# 3__Output_Feedback.net
KiCad netlist of a schematic drawn in Altium Designer
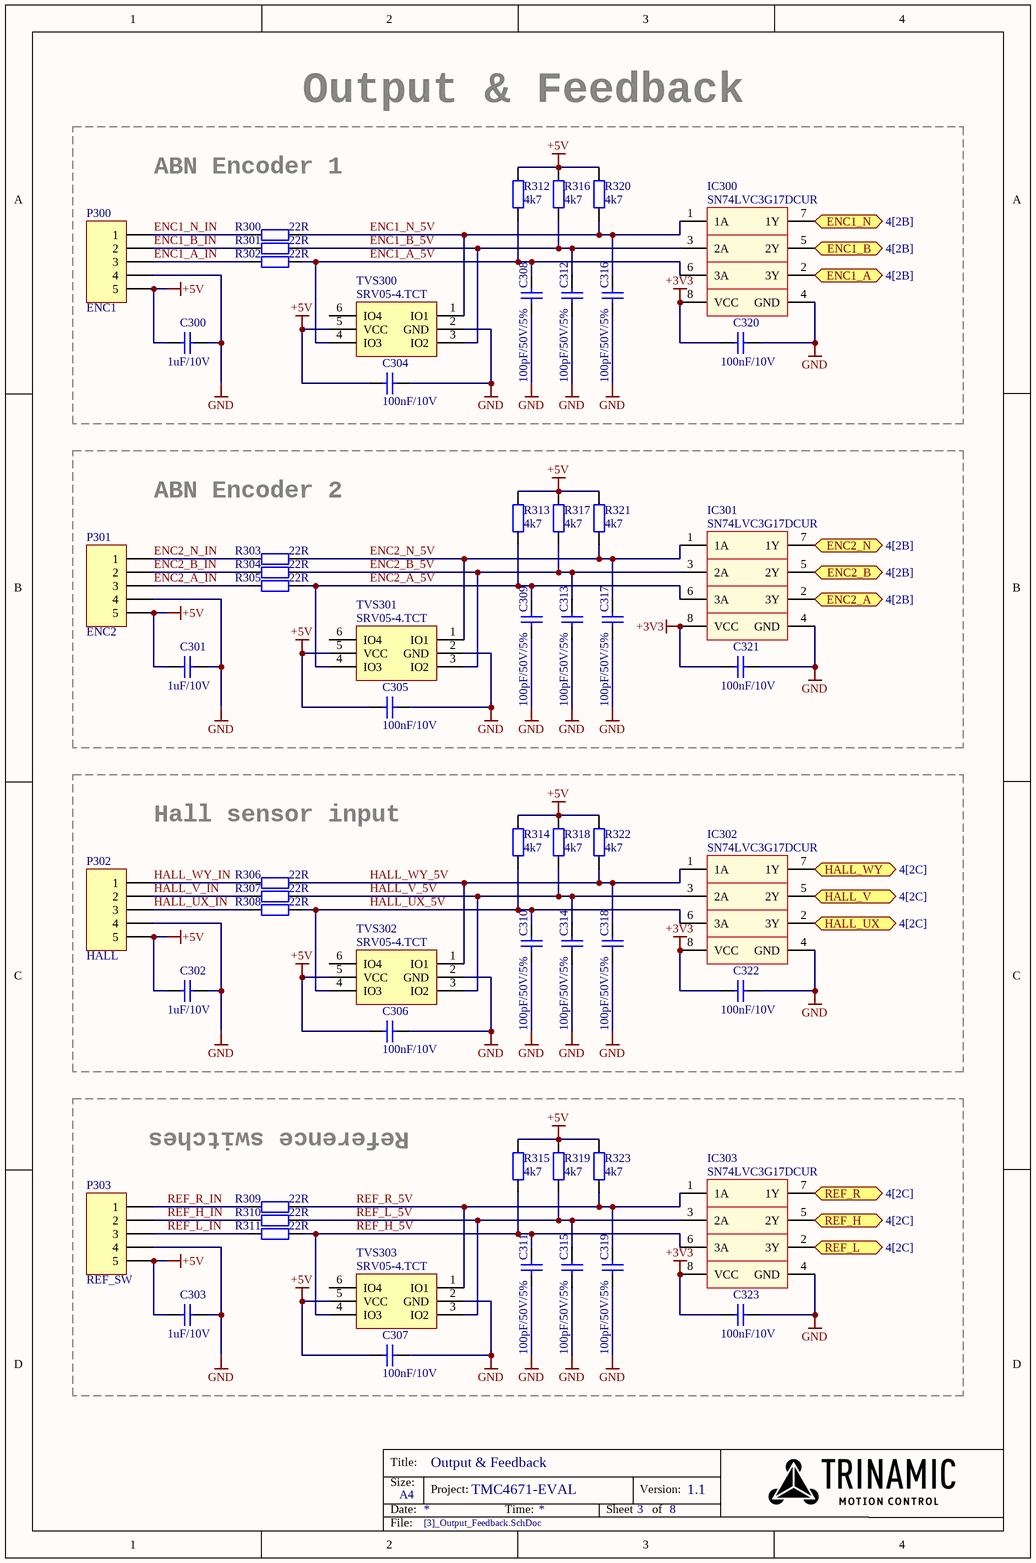
[diagram p0: [3]_Output_Feedback.SchDoc]

(export (version "E")
  (design (tool "Eeschema 10.0.6"))
  (components
    (comp (ref "C300")
      (value "1uF/10V")
      (footprint "C0603")
      (description "SMD Multilayer Ceramic Capacitor, 0603 [1608 Metric], 1 µF, 10 V, ± 10%, X5R, MC Series")
      (fields (field (name "MF") "MULTICOMP") (field (name "MPN") "MC0603X105K100CT"))
      (libsource (lib "SMD_Passives") (part "C, 1 µF, 10 V, ± 10%, X5R, MC Series, 0603 [1608 Metric]"))
    )
    (comp (ref "C301")
      (value "1uF/10V")
      (footprint "C0603")
      (description "SMD Multilayer Ceramic Capacitor, 0603 [1608 Metric], 1 µF, 10 V, ± 10%, X5R, MC Series")
      (fields (field (name "MF") "MULTICOMP") (field (name "MPN") "MC0603X105K100CT"))
      (libsource (lib "SMD_Passives") (part "C, 1 µF, 10 V, ± 10%, X5R, MC Series, 0603 [1608 Metric]"))
    )
    (comp (ref "C302")
      (value "1uF/10V")
      (footprint "C0603")
      (description "SMD Multilayer Ceramic Capacitor, 0603 [1608 Metric], 1 µF, 10 V, ± 10%, X5R, MC Series")
      (fields (field (name "MF") "MULTICOMP") (field (name "MPN") "MC0603X105K100CT"))
      (libsource (lib "SMD_Passives") (part "C, 1 µF, 10 V, ± 10%, X5R, MC Series, 0603 [1608 Metric]"))
    )
    (comp (ref "C303")
      (value "1uF/10V")
      (footprint "C0603")
      (description "SMD Multilayer Ceramic Capacitor, 0603 [1608 Metric], 1 µF, 10 V, ± 10%, X5R, MC Series")
      (fields (field (name "MF") "MULTICOMP") (field (name "MPN") "MC0603X105K100CT"))
      (libsource (lib "SMD_Passives") (part "C, 1 µF, 10 V, ± 10%, X5R, MC Series, 0603 [1608 Metric]"))
    )
    (comp (ref "C304")
      (value "100nF/10V")
      (footprint "C0603")
      (description "SMD Multilayer Ceramic Capacitor, 0603 [1608 Metric], 0.1 µF, 10 V, ± 10%, X7R, MC Series")
      (fields (field (name "MF") "Multicomp") (field (name "MPN") "MC0603B104K100CT"))
      (libsource (lib "SMD_Passives") (part "C, 0.1 µF, 10 V, ± 10%, X7R, 0603"))
    )
    (comp (ref "C305")
      (value "100nF/10V")
      (footprint "C0603")
      (description "SMD Multilayer Ceramic Capacitor, 0603 [1608 Metric], 0.1 µF, 10 V, ± 10%, X7R, MC Series")
      (fields (field (name "MF") "Multicomp") (field (name "MPN") "MC0603B104K100CT"))
      (libsource (lib "SMD_Passives") (part "C, 0.1 µF, 10 V, ± 10%, X7R, 0603"))
    )
    (comp (ref "C306")
      (value "100nF/10V")
      (footprint "C0603")
      (description "SMD Multilayer Ceramic Capacitor, 0603 [1608 Metric], 0.1 µF, 10 V, ± 10%, X7R, MC Series")
      (fields (field (name "MF") "Multicomp") (field (name "MPN") "MC0603B104K100CT"))
      (libsource (lib "SMD_Passives") (part "C, 0.1 µF, 10 V, ± 10%, X7R, 0603"))
    )
    (comp (ref "C307")
      (value "100nF/10V")
      (footprint "C0603")
      (description "SMD Multilayer Ceramic Capacitor, 0603 [1608 Metric], 0.1 µF, 10 V, ± 10%, X7R, MC Series")
      (fields (field (name "MF") "Multicomp") (field (name "MPN") "MC0603B104K100CT"))
      (libsource (lib "SMD_Passives") (part "C, 0.1 µF, 10 V, ± 10%, X7R, 0603"))
    )
    (comp (ref "C308")
      (value "100pF/50V/5%")
      (footprint "C0603")
      (description "SMD Multilayer Ceramic Capacitor, 0603 [1608 Metric], 100 pF, 50 V, ± 5%, C0G / NP0, MC Series")
      (fields (field (name "MF") "MULTICOMP") (field (name "MPN") "MC0603N101J500CT"))
      (libsource (lib "SMD_Passives") (part "C, 100 pF, 50 V, ± 5%, C0G / NP0, MC Series, 0603 [1608 Metric]"))
    )
    (comp (ref "C309")
      (value "100pF/50V/5%")
      (footprint "C0603")
      (description "SMD Multilayer Ceramic Capacitor, 0603 [1608 Metric], 100 pF, 50 V, ± 5%, C0G / NP0, MC Series")
      (fields (field (name "MF") "MULTICOMP") (field (name "MPN") "MC0603N101J500CT"))
      (libsource (lib "SMD_Passives") (part "C, 100 pF, 50 V, ± 5%, C0G / NP0, MC Series, 0603 [1608 Metric]"))
    )
    (comp (ref "C310")
      (value "100pF/50V/5%")
      (footprint "C0603")
      (description "SMD Multilayer Ceramic Capacitor, 0603 [1608 Metric], 100 pF, 50 V, ± 5%, C0G / NP0, MC Series")
      (fields (field (name "MF") "MULTICOMP") (field (name "MPN") "MC0603N101J500CT"))
      (libsource (lib "SMD_Passives") (part "C, 100 pF, 50 V, ± 5%, C0G / NP0, MC Series, 0603 [1608 Metric]"))
    )
    (comp (ref "C311")
      (value "100pF/50V/5%")
      (footprint "C0603")
      (description "SMD Multilayer Ceramic Capacitor, 0603 [1608 Metric], 100 pF, 50 V, ± 5%, C0G / NP0, MC Series")
      (fields (field (name "MF") "MULTICOMP") (field (name "MPN") "MC0603N101J500CT"))
      (libsource (lib "SMD_Passives") (part "C, 100 pF, 50 V, ± 5%, C0G / NP0, MC Series, 0603 [1608 Metric]"))
    )
    (comp (ref "C312")
      (value "100pF/50V/5%")
      (footprint "C0603")
      (description "SMD Multilayer Ceramic Capacitor, 0603 [1608 Metric], 100 pF, 50 V, ± 5%, C0G / NP0, MC Series")
      (fields (field (name "MF") "MULTICOMP") (field (name "MPN") "MC0603N101J500CT"))
      (libsource (lib "SMD_Passives") (part "C, 100 pF, 50 V, ± 5%, C0G / NP0, MC Series, 0603 [1608 Metric]"))
    )
    (comp (ref "C313")
      (value "100pF/50V/5%")
      (footprint "C0603")
      (description "SMD Multilayer Ceramic Capacitor, 0603 [1608 Metric], 100 pF, 50 V, ± 5%, C0G / NP0, MC Series")
      (fields (field (name "MF") "MULTICOMP") (field (name "MPN") "MC0603N101J500CT"))
      (libsource (lib "SMD_Passives") (part "C, 100 pF, 50 V, ± 5%, C0G / NP0, MC Series, 0603 [1608 Metric]"))
    )
    (comp (ref "C314")
      (value "100pF/50V/5%")
      (footprint "C0603")
      (description "SMD Multilayer Ceramic Capacitor, 0603 [1608 Metric], 100 pF, 50 V, ± 5%, C0G / NP0, MC Series")
      (fields (field (name "MF") "MULTICOMP") (field (name "MPN") "MC0603N101J500CT"))
      (libsource (lib "SMD_Passives") (part "C, 100 pF, 50 V, ± 5%, C0G / NP0, MC Series, 0603 [1608 Metric]"))
    )
    (comp (ref "C315")
      (value "100pF/50V/5%")
      (footprint "C0603")
      (description "SMD Multilayer Ceramic Capacitor, 0603 [1608 Metric], 100 pF, 50 V, ± 5%, C0G / NP0, MC Series")
      (fields (field (name "MF") "MULTICOMP") (field (name "MPN") "MC0603N101J500CT"))
      (libsource (lib "SMD_Passives") (part "C, 100 pF, 50 V, ± 5%, C0G / NP0, MC Series, 0603 [1608 Metric]"))
    )
    (comp (ref "C316")
      (value "100pF/50V/5%")
      (footprint "C0603")
      (description "SMD Multilayer Ceramic Capacitor, 0603 [1608 Metric], 100 pF, 50 V, ± 5%, C0G / NP0, MC Series")
      (fields (field (name "MF") "MULTICOMP") (field (name "MPN") "MC0603N101J500CT"))
      (libsource (lib "SMD_Passives") (part "C, 100 pF, 50 V, ± 5%, C0G / NP0, MC Series, 0603 [1608 Metric]"))
    )
    (comp (ref "C317")
      (value "100pF/50V/5%")
      (footprint "C0603")
      (description "SMD Multilayer Ceramic Capacitor, 0603 [1608 Metric], 100 pF, 50 V, ± 5%, C0G / NP0, MC Series")
      (fields (field (name "MF") "MULTICOMP") (field (name "MPN") "MC0603N101J500CT"))
      (libsource (lib "SMD_Passives") (part "C, 100 pF, 50 V, ± 5%, C0G / NP0, MC Series, 0603 [1608 Metric]"))
    )
    (comp (ref "C318")
      (value "100pF/50V/5%")
      (footprint "C0603")
      (description "SMD Multilayer Ceramic Capacitor, 0603 [1608 Metric], 100 pF, 50 V, ± 5%, C0G / NP0, MC Series")
      (fields (field (name "MF") "MULTICOMP") (field (name "MPN") "MC0603N101J500CT"))
      (libsource (lib "SMD_Passives") (part "C, 100 pF, 50 V, ± 5%, C0G / NP0, MC Series, 0603 [1608 Metric]"))
    )
    (comp (ref "C319")
      (value "100pF/50V/5%")
      (footprint "C0603")
      (description "SMD Multilayer Ceramic Capacitor, 0603 [1608 Metric], 100 pF, 50 V, ± 5%, C0G / NP0, MC Series")
      (fields (field (name "MF") "MULTICOMP") (field (name "MPN") "MC0603N101J500CT"))
      (libsource (lib "SMD_Passives") (part "C, 100 pF, 50 V, ± 5%, C0G / NP0, MC Series, 0603 [1608 Metric]"))
    )
    (comp (ref "C320")
      (value "100nF/10V")
      (footprint "C0603")
      (description "SMD Multilayer Ceramic Capacitor, 0603 [1608 Metric], 0.1 µF, 10 V, ± 10%, X7R, MC Series")
      (fields (field (name "MF") "Multicomp") (field (name "MPN") "MC0603B104K100CT"))
      (libsource (lib "SMD_Passives") (part "C, 0.1 µF, 10 V, ± 10%, X7R, 0603"))
    )
    (comp (ref "C321")
      (value "100nF/10V")
      (footprint "C0603")
      (description "SMD Multilayer Ceramic Capacitor, 0603 [1608 Metric], 0.1 µF, 10 V, ± 10%, X7R, MC Series")
      (fields (field (name "MF") "Multicomp") (field (name "MPN") "MC0603B104K100CT"))
      (libsource (lib "SMD_Passives") (part "C, 0.1 µF, 10 V, ± 10%, X7R, 0603"))
    )
    (comp (ref "C322")
      (value "100nF/10V")
      (footprint "C0603")
      (description "SMD Multilayer Ceramic Capacitor, 0603 [1608 Metric], 0.1 µF, 10 V, ± 10%, X7R, MC Series")
      (fields (field (name "MF") "Multicomp") (field (name "MPN") "MC0603B104K100CT"))
      (libsource (lib "SMD_Passives") (part "C, 0.1 µF, 10 V, ± 10%, X7R, 0603"))
    )
    (comp (ref "C323")
      (value "100nF/10V")
      (footprint "C0603")
      (description "SMD Multilayer Ceramic Capacitor, 0603 [1608 Metric], 0.1 µF, 10 V, ± 10%, X7R, MC Series")
      (fields (field (name "MF") "Multicomp") (field (name "MPN") "MC0603B104K100CT"))
      (libsource (lib "SMD_Passives") (part "C, 0.1 µF, 10 V, ± 10%, X7R, 0603"))
    )
    (comp (ref "IC300")
      (value "SN74LVC3G17DCUR")
      (footprint "TSSOP50P310X90-8L")
      (description "Triple Schmitt-Trigger Buffer, 74LVC3G17, 1.65 V to 5.5 V, VSSOP-8")
      (fields (field (name "MF") "TEXAS INSTRUMENTS"))
      (libsource (lib "TMC4671-EVAL_V1_0") (part "SN74LVC3G17DCUR"))
    )
    (comp (ref "IC301")
      (value "SN74LVC3G17DCUR")
      (footprint "TSSOP50P310X90-8L")
      (description "Triple Schmitt-Trigger Buffer, 74LVC3G17, 1.65 V to 5.5 V, VSSOP-8")
      (fields (field (name "MF") "TEXAS INSTRUMENTS"))
      (libsource (lib "TMC4671-EVAL_V1_0") (part "SN74LVC3G17DCUR"))
    )
    (comp (ref "IC302")
      (value "SN74LVC3G17DCUR")
      (footprint "TSSOP50P310X90-8L")
      (description "Triple Schmitt-Trigger Buffer, 74LVC3G17, 1.65 V to 5.5 V, VSSOP-8")
      (fields (field (name "MF") "TEXAS INSTRUMENTS"))
      (libsource (lib "TMC4671-EVAL_V1_0") (part "SN74LVC3G17DCUR"))
    )
    (comp (ref "IC303")
      (value "SN74LVC3G17DCUR")
      (footprint "TSSOP50P310X90-8L")
      (description "Triple Schmitt-Trigger Buffer, 74LVC3G17, 1.65 V to 5.5 V, VSSOP-8")
      (fields (field (name "MF") "TEXAS INSTRUMENTS"))
      (libsource (lib "TMC4671-EVAL_V1_0") (part "SN74LVC3G17DCUR"))
    )
    (comp (ref "P300")
      (value "ENC1")
      (footprint "TH_HDR_1X5")
      (description "Header, 5-Pin")
      (libsource (lib "Miscellaneous Connectors") (part "Header 5"))
    )
    (comp (ref "P301")
      (value "ENC2")
      (footprint "TH_HDR_1X5")
      (description "Header, 5-Pin")
      (libsource (lib "Miscellaneous Connectors") (part "Header 5"))
    )
    (comp (ref "P302")
      (value "HALL")
      (footprint "TH_HDR_1X5")
      (description "Header, 5-Pin")
      (libsource (lib "Miscellaneous Connectors") (part "Header 5"))
    )
    (comp (ref "P303")
      (value "REF_SW")
      (footprint "TH_HDR_1X5")
      (description "Header, 5-Pin")
      (libsource (lib "Miscellaneous Connectors") (part "Header 5"))
    )
    (comp (ref "R300")
      (value "22R")
      (footprint "R0603")
      (description "SMD Chip Resistor, Thick Film, 22 ohm, 50 V, 0603 [1608 Metric], 100 mW, ± 1%, MCWR Series")
      (fields
        (field (name "MPN") "MCWR06X22R0FTL")
        (field (name "MF") "MULTICOMP")
        (field (name "RESISTANCE") "22R")
      )
      (libsource (lib "SMD_Passives") (part "R, 22 ohm, 50 V, 0603 [1608 Metric], 100 mW, ± 1%, MCWR Series"))
    )
    (comp (ref "R301")
      (value "22R")
      (footprint "R0603")
      (description "SMD Chip Resistor, Thick Film, 22 ohm, 50 V, 0603 [1608 Metric], 100 mW, ± 1%, MCWR Series")
      (fields
        (field (name "MPN") "MCWR06X22R0FTL")
        (field (name "MF") "MULTICOMP")
        (field (name "RESISTANCE") "22R")
      )
      (libsource (lib "SMD_Passives") (part "R, 22 ohm, 50 V, 0603 [1608 Metric], 100 mW, ± 1%, MCWR Series"))
    )
    (comp (ref "R302")
      (value "22R")
      (footprint "R0603")
      (description "SMD Chip Resistor, Thick Film, 22 ohm, 50 V, 0603 [1608 Metric], 100 mW, ± 1%, MCWR Series")
      (fields
        (field (name "MPN") "MCWR06X22R0FTL")
        (field (name "MF") "MULTICOMP")
        (field (name "RESISTANCE") "22R")
      )
      (libsource (lib "SMD_Passives") (part "R, 22 ohm, 50 V, 0603 [1608 Metric], 100 mW, ± 1%, MCWR Series"))
    )
    (comp (ref "R303")
      (value "22R")
      (footprint "R0603")
      (description "SMD Chip Resistor, Thick Film, 22 ohm, 50 V, 0603 [1608 Metric], 100 mW, ± 1%, MCWR Series")
      (fields
        (field (name "MPN") "MCWR06X22R0FTL")
        (field (name "MF") "MULTICOMP")
        (field (name "RESISTANCE") "22R")
      )
      (libsource (lib "SMD_Passives") (part "R, 22 ohm, 50 V, 0603 [1608 Metric], 100 mW, ± 1%, MCWR Series"))
    )
    (comp (ref "R304")
      (value "22R")
      (footprint "R0603")
      (description "SMD Chip Resistor, Thick Film, 22 ohm, 50 V, 0603 [1608 Metric], 100 mW, ± 1%, MCWR Series")
      (fields
        (field (name "MPN") "MCWR06X22R0FTL")
        (field (name "MF") "MULTICOMP")
        (field (name "RESISTANCE") "22R")
      )
      (libsource (lib "SMD_Passives") (part "R, 22 ohm, 50 V, 0603 [1608 Metric], 100 mW, ± 1%, MCWR Series"))
    )
    (comp (ref "R305")
      (value "22R")
      (footprint "R0603")
      (description "SMD Chip Resistor, Thick Film, 22 ohm, 50 V, 0603 [1608 Metric], 100 mW, ± 1%, MCWR Series")
      (fields
        (field (name "MPN") "MCWR06X22R0FTL")
        (field (name "MF") "MULTICOMP")
        (field (name "RESISTANCE") "22R")
      )
      (libsource (lib "SMD_Passives") (part "R, 22 ohm, 50 V, 0603 [1608 Metric], 100 mW, ± 1%, MCWR Series"))
    )
    (comp (ref "R306")
      (value "22R")
      (footprint "R0603")
      (description "SMD Chip Resistor, Thick Film, 22 ohm, 50 V, 0603 [1608 Metric], 100 mW, ± 1%, MCWR Series")
      (fields
        (field (name "MPN") "MCWR06X22R0FTL")
        (field (name "MF") "MULTICOMP")
        (field (name "RESISTANCE") "22R")
      )
      (libsource (lib "SMD_Passives") (part "R, 22 ohm, 50 V, 0603 [1608 Metric], 100 mW, ± 1%, MCWR Series"))
    )
    (comp (ref "R307")
      (value "22R")
      (footprint "R0603")
      (description "SMD Chip Resistor, Thick Film, 22 ohm, 50 V, 0603 [1608 Metric], 100 mW, ± 1%, MCWR Series")
      (fields
        (field (name "MPN") "MCWR06X22R0FTL")
        (field (name "MF") "MULTICOMP")
        (field (name "RESISTANCE") "22R")
      )
      (libsource (lib "SMD_Passives") (part "R, 22 ohm, 50 V, 0603 [1608 Metric], 100 mW, ± 1%, MCWR Series"))
    )
    (comp (ref "R308")
      (value "22R")
      (footprint "R0603")
      (description "SMD Chip Resistor, Thick Film, 22 ohm, 50 V, 0603 [1608 Metric], 100 mW, ± 1%, MCWR Series")
      (fields
        (field (name "MPN") "MCWR06X22R0FTL")
        (field (name "MF") "MULTICOMP")
        (field (name "RESISTANCE") "22R")
      )
      (libsource (lib "SMD_Passives") (part "R, 22 ohm, 50 V, 0603 [1608 Metric], 100 mW, ± 1%, MCWR Series"))
    )
    (comp (ref "R309")
      (value "22R")
      (footprint "R0603")
      (description "SMD Chip Resistor, Thick Film, 22 ohm, 50 V, 0603 [1608 Metric], 100 mW, ± 1%, MCWR Series")
      (fields
        (field (name "MPN") "MCWR06X22R0FTL")
        (field (name "MF") "MULTICOMP")
        (field (name "RESISTANCE") "22R")
      )
      (libsource (lib "SMD_Passives") (part "R, 22 ohm, 50 V, 0603 [1608 Metric], 100 mW, ± 1%, MCWR Series"))
    )
    (comp (ref "R310")
      (value "22R")
      (footprint "R0603")
      (description "SMD Chip Resistor, Thick Film, 22 ohm, 50 V, 0603 [1608 Metric], 100 mW, ± 1%, MCWR Series")
      (fields
        (field (name "MPN") "MCWR06X22R0FTL")
        (field (name "MF") "MULTICOMP")
        (field (name "RESISTANCE") "22R")
      )
      (libsource (lib "SMD_Passives") (part "R, 22 ohm, 50 V, 0603 [1608 Metric], 100 mW, ± 1%, MCWR Series"))
    )
    (comp (ref "R311")
      (value "22R")
      (footprint "R0603")
      (description "SMD Chip Resistor, Thick Film, 22 ohm, 50 V, 0603 [1608 Metric], 100 mW, ± 1%, MCWR Series")
      (fields
        (field (name "MPN") "MCWR06X22R0FTL")
        (field (name "MF") "MULTICOMP")
        (field (name "RESISTANCE") "22R")
      )
      (libsource (lib "SMD_Passives") (part "R, 22 ohm, 50 V, 0603 [1608 Metric], 100 mW, ± 1%, MCWR Series"))
    )
    (comp (ref "R312")
      (value "4k7")
      (footprint "R0603")
      (description "SMD Chip Resistor, 4.7 kohm, 75 V, 0603 [1608 Metric], 100 mW, ± 1%, WR06 Series")
      (fields
        (field (name "MPN") "WR06X4701FTL")
        (field (name "MF") "WALSIN")
        (field (name "RESISTANCE") "4k7")
      )
      (libsource (lib "SMD_Passives") (part "R, 4.7 kohm, 75 V, 0603 [1608 Metric], 100 mW, ± 1%, WR06 Series"))
    )
    (comp (ref "R313")
      (value "4k7")
      (footprint "R0603")
      (description "SMD Chip Resistor, 4.7 kohm, 75 V, 0603 [1608 Metric], 100 mW, ± 1%, WR06 Series")
      (fields
        (field (name "MPN") "WR06X4701FTL")
        (field (name "MF") "WALSIN")
        (field (name "RESISTANCE") "4k7")
      )
      (libsource (lib "SMD_Passives") (part "R, 4.7 kohm, 75 V, 0603 [1608 Metric], 100 mW, ± 1%, WR06 Series"))
    )
    (comp (ref "R314")
      (value "4k7")
      (footprint "R0603")
      (description "SMD Chip Resistor, 4.7 kohm, 75 V, 0603 [1608 Metric], 100 mW, ± 1%, WR06 Series")
      (fields
        (field (name "MPN") "WR06X4701FTL")
        (field (name "MF") "WALSIN")
        (field (name "RESISTANCE") "4k7")
      )
      (libsource (lib "SMD_Passives") (part "R, 4.7 kohm, 75 V, 0603 [1608 Metric], 100 mW, ± 1%, WR06 Series"))
    )
    (comp (ref "R315")
      (value "4k7")
      (footprint "R0603")
      (description "SMD Chip Resistor, 4.7 kohm, 75 V, 0603 [1608 Metric], 100 mW, ± 1%, WR06 Series")
      (fields
        (field (name "MPN") "WR06X4701FTL")
        (field (name "MF") "WALSIN")
        (field (name "RESISTANCE") "4k7")
      )
      (libsource (lib "SMD_Passives") (part "R, 4.7 kohm, 75 V, 0603 [1608 Metric], 100 mW, ± 1%, WR06 Series"))
    )
    (comp (ref "R316")
      (value "4k7")
      (footprint "R0603")
      (description "SMD Chip Resistor, 4.7 kohm, 75 V, 0603 [1608 Metric], 100 mW, ± 1%, WR06 Series")
      (fields
        (field (name "MPN") "WR06X4701FTL")
        (field (name "MF") "WALSIN")
        (field (name "RESISTANCE") "4k7")
      )
      (libsource (lib "SMD_Passives") (part "R, 4.7 kohm, 75 V, 0603 [1608 Metric], 100 mW, ± 1%, WR06 Series"))
    )
    (comp (ref "R317")
      (value "4k7")
      (footprint "R0603")
      (description "SMD Chip Resistor, 4.7 kohm, 75 V, 0603 [1608 Metric], 100 mW, ± 1%, WR06 Series")
      (fields
        (field (name "MPN") "WR06X4701FTL")
        (field (name "MF") "WALSIN")
        (field (name "RESISTANCE") "4k7")
      )
      (libsource (lib "SMD_Passives") (part "R, 4.7 kohm, 75 V, 0603 [1608 Metric], 100 mW, ± 1%, WR06 Series"))
    )
    (comp (ref "R318")
      (value "4k7")
      (footprint "R0603")
      (description "SMD Chip Resistor, 4.7 kohm, 75 V, 0603 [1608 Metric], 100 mW, ± 1%, WR06 Series")
      (fields
        (field (name "MPN") "WR06X4701FTL")
        (field (name "MF") "WALSIN")
        (field (name "RESISTANCE") "4k7")
      )
      (libsource (lib "SMD_Passives") (part "R, 4.7 kohm, 75 V, 0603 [1608 Metric], 100 mW, ± 1%, WR06 Series"))
    )
    (comp (ref "R319")
      (value "4k7")
      (footprint "R0603")
      (description "SMD Chip Resistor, 4.7 kohm, 75 V, 0603 [1608 Metric], 100 mW, ± 1%, WR06 Series")
      (fields
        (field (name "MPN") "WR06X4701FTL")
        (field (name "MF") "WALSIN")
        (field (name "RESISTANCE") "4k7")
      )
      (libsource (lib "SMD_Passives") (part "R, 4.7 kohm, 75 V, 0603 [1608 Metric], 100 mW, ± 1%, WR06 Series"))
    )
    (comp (ref "R320")
      (value "4k7")
      (footprint "R0603")
      (description "SMD Chip Resistor, 4.7 kohm, 75 V, 0603 [1608 Metric], 100 mW, ± 1%, WR06 Series")
      (fields
        (field (name "MPN") "WR06X4701FTL")
        (field (name "MF") "WALSIN")
        (field (name "RESISTANCE") "4k7")
      )
      (libsource (lib "SMD_Passives") (part "R, 4.7 kohm, 75 V, 0603 [1608 Metric], 100 mW, ± 1%, WR06 Series"))
    )
    (comp (ref "R321")
      (value "4k7")
      (footprint "R0603")
      (description "SMD Chip Resistor, 4.7 kohm, 75 V, 0603 [1608 Metric], 100 mW, ± 1%, WR06 Series")
      (fields
        (field (name "MPN") "WR06X4701FTL")
        (field (name "MF") "WALSIN")
        (field (name "RESISTANCE") "4k7")
      )
      (libsource (lib "SMD_Passives") (part "R, 4.7 kohm, 75 V, 0603 [1608 Metric], 100 mW, ± 1%, WR06 Series"))
    )
    (comp (ref "R322")
      (value "4k7")
      (footprint "R0603")
      (description "SMD Chip Resistor, 4.7 kohm, 75 V, 0603 [1608 Metric], 100 mW, ± 1%, WR06 Series")
      (fields
        (field (name "MPN") "WR06X4701FTL")
        (field (name "MF") "WALSIN")
        (field (name "RESISTANCE") "4k7")
      )
      (libsource (lib "SMD_Passives") (part "R, 4.7 kohm, 75 V, 0603 [1608 Metric], 100 mW, ± 1%, WR06 Series"))
    )
    (comp (ref "R323")
      (value "4k7")
      (footprint "R0603")
      (description "SMD Chip Resistor, 4.7 kohm, 75 V, 0603 [1608 Metric], 100 mW, ± 1%, WR06 Series")
      (fields
        (field (name "MPN") "WR06X4701FTL")
        (field (name "MF") "WALSIN")
        (field (name "RESISTANCE") "4k7")
      )
      (libsource (lib "SMD_Passives") (part "R, 4.7 kohm, 75 V, 0603 [1608 Metric], 100 mW, ± 1%, WR06 Series"))
    )
    (comp (ref "TVS300")
      (value "SRV05-4.TCT")
      (footprint "SOT95P280X145-6N")
      (description "ESD Protection Device, TVS, 17.5 V, SOT-23, 6 Pins, 5 V, 300 W")
      (fields (field (name "MF") "SEMTECH"))
      (libsource (lib "TMC4671-EVAL_V1_0") (part "ESD, TVS, SRV05-4.TCT"))
    )
    (comp (ref "TVS301")
      (value "SRV05-4.TCT")
      (footprint "SOT95P280X145-6N")
      (description "ESD Protection Device, TVS, 17.5 V, SOT-23, 6 Pins, 5 V, 300 W")
      (fields (field (name "MF") "SEMTECH"))
      (libsource (lib "TMC4671-EVAL_V1_0") (part "ESD, TVS, SRV05-4.TCT"))
    )
    (comp (ref "TVS302")
      (value "SRV05-4.TCT")
      (footprint "SOT95P280X145-6N")
      (description "ESD Protection Device, TVS, 17.5 V, SOT-23, 6 Pins, 5 V, 300 W")
      (fields (field (name "MF") "SEMTECH"))
      (libsource (lib "TMC4671-EVAL_V1_0") (part "ESD, TVS, SRV05-4.TCT"))
    )
    (comp (ref "TVS303")
      (value "SRV05-4.TCT")
      (footprint "SOT95P280X145-6N")
      (description "ESD Protection Device, TVS, 17.5 V, SOT-23, 6 Pins, 5 V, 300 W")
      (fields (field (name "MF") "SEMTECH"))
      (libsource (lib "TMC4671-EVAL_V1_0") (part "ESD, TVS, SRV05-4.TCT"))
    )
  )
  (nets
    (net (code "1") (name "+3V3") (class "Default")
      (node (ref "C320") (pin "2") (pinfunction "2_2") (pintype "passive"))
      (node (ref "C321") (pin "2") (pinfunction "2_2") (pintype "passive"))
      (node (ref "C322") (pin "2") (pinfunction "2_2") (pintype "passive"))
      (node (ref "C323") (pin "2") (pinfunction "2_2") (pintype "passive"))
      (node (ref "IC300") (pin "8") (pinfunction "VCC_8") (pintype "power_in"))
      (node (ref "IC301") (pin "8") (pinfunction "VCC_8") (pintype "power_in"))
      (node (ref "IC302") (pin "8") (pinfunction "VCC_8") (pintype "power_in"))
      (node (ref "IC303") (pin "8") (pinfunction "VCC_8") (pintype "power_in"))
    )
    (net (code "2") (name "+5V") (class "Default")
      (node (ref "C300") (pin "2") (pinfunction "2_2") (pintype "passive"))
      (node (ref "C301") (pin "2") (pinfunction "2_2") (pintype "passive"))
      (node (ref "C302") (pin "2") (pinfunction "2_2") (pintype "passive"))
      (node (ref "C303") (pin "2") (pinfunction "2_2") (pintype "passive"))
      (node (ref "C304") (pin "1") (pinfunction "1_1") (pintype "passive"))
      (node (ref "C305") (pin "1") (pinfunction "1_1") (pintype "passive"))
      (node (ref "C306") (pin "1") (pinfunction "1_1") (pintype "passive"))
      (node (ref "C307") (pin "1") (pinfunction "1_1") (pintype "passive"))
      (node (ref "P300") (pin "5") (pinfunction "5_5") (pintype "passive"))
      (node (ref "P301") (pin "5") (pinfunction "5_5") (pintype "passive"))
      (node (ref "P302") (pin "5") (pinfunction "5_5") (pintype "passive"))
      (node (ref "P303") (pin "5") (pinfunction "5_5") (pintype "passive"))
      (node (ref "R312") (pin "2") (pinfunction "2_2") (pintype "passive"))
      (node (ref "R313") (pin "2") (pinfunction "2_2") (pintype "passive"))
      (node (ref "R314") (pin "2") (pinfunction "2_2") (pintype "passive"))
      (node (ref "R315") (pin "2") (pinfunction "2_2") (pintype "passive"))
      (node (ref "R316") (pin "2") (pinfunction "2_2") (pintype "passive"))
      (node (ref "R317") (pin "2") (pinfunction "2_2") (pintype "passive"))
      (node (ref "R318") (pin "2") (pinfunction "2_2") (pintype "passive"))
      (node (ref "R319") (pin "2") (pinfunction "2_2") (pintype "passive"))
      (node (ref "R320") (pin "2") (pinfunction "2_2") (pintype "passive"))
      (node (ref "R321") (pin "2") (pinfunction "2_2") (pintype "passive"))
      (node (ref "R322") (pin "2") (pinfunction "2_2") (pintype "passive"))
      (node (ref "R323") (pin "2") (pinfunction "2_2") (pintype "passive"))
      (node (ref "TVS300") (pin "5") (pinfunction "VCC_5") (pintype "passive"))
      (node (ref "TVS301") (pin "5") (pinfunction "VCC_5") (pintype "passive"))
      (node (ref "TVS302") (pin "5") (pinfunction "VCC_5") (pintype "passive"))
      (node (ref "TVS303") (pin "5") (pinfunction "VCC_5") (pintype "passive"))
    )
    (net (code "3") (name "/ENC1_A") (class "Default")
      (node (ref "IC300") (pin "2") (pinfunction "3Y_2") (pintype "power_in"))
    )
    (net (code "4") (name "/ENC1_A_5V") (class "Default")
      (node (ref "C308") (pin "2") (pinfunction "2_2") (pintype "passive"))
      (node (ref "IC300") (pin "6") (pinfunction "3A_6") (pintype "power_in"))
      (node (ref "R302") (pin "1") (pinfunction "1_1") (pintype "passive"))
      (node (ref "R312") (pin "1") (pinfunction "1_1") (pintype "passive"))
      (node (ref "TVS300") (pin "4") (pinfunction "IO3_4") (pintype "passive"))
    )
    (net (code "5") (name "/ENC1_A_IN") (class "Default")
      (node (ref "P300") (pin "3") (pinfunction "3_3") (pintype "passive"))
      (node (ref "R302") (pin "2") (pinfunction "2_2") (pintype "passive"))
    )
    (net (code "6") (name "/ENC1_B") (class "Default")
      (node (ref "IC300") (pin "5") (pinfunction "2Y_5") (pintype "power_in"))
    )
    (net (code "7") (name "/ENC1_B_5V") (class "Default")
      (node (ref "C312") (pin "2") (pinfunction "2_2") (pintype "passive"))
      (node (ref "IC300") (pin "3") (pinfunction "2A_3") (pintype "power_in"))
      (node (ref "R301") (pin "1") (pinfunction "1_1") (pintype "passive"))
      (node (ref "R316") (pin "1") (pinfunction "1_1") (pintype "passive"))
      (node (ref "TVS300") (pin "3") (pinfunction "IO2_3") (pintype "passive"))
    )
    (net (code "8") (name "/ENC1_B_IN") (class "Default")
      (node (ref "P300") (pin "2") (pinfunction "2_2") (pintype "passive"))
      (node (ref "R301") (pin "2") (pinfunction "2_2") (pintype "passive"))
    )
    (net (code "9") (name "/ENC1_N") (class "Default")
      (node (ref "IC300") (pin "7") (pinfunction "1Y_7") (pintype "power_in"))
    )
    (net (code "10") (name "/ENC1_N_5V") (class "Default")
      (node (ref "C316") (pin "2") (pinfunction "2_2") (pintype "passive"))
      (node (ref "IC300") (pin "1") (pinfunction "1A_1") (pintype "power_in"))
      (node (ref "R300") (pin "1") (pinfunction "1_1") (pintype "passive"))
      (node (ref "R320") (pin "1") (pinfunction "1_1") (pintype "passive"))
      (node (ref "TVS300") (pin "1") (pinfunction "IO1_1") (pintype "passive"))
    )
    (net (code "11") (name "/ENC1_N_IN") (class "Default")
      (node (ref "P300") (pin "1") (pinfunction "1_1") (pintype "passive"))
      (node (ref "R300") (pin "2") (pinfunction "2_2") (pintype "passive"))
    )
    (net (code "12") (name "/ENC2_A") (class "Default")
      (node (ref "IC301") (pin "2") (pinfunction "3Y_2") (pintype "power_in"))
    )
    (net (code "13") (name "/ENC2_A_5V") (class "Default")
      (node (ref "C309") (pin "2") (pinfunction "2_2") (pintype "passive"))
      (node (ref "IC301") (pin "6") (pinfunction "3A_6") (pintype "power_in"))
      (node (ref "R305") (pin "1") (pinfunction "1_1") (pintype "passive"))
      (node (ref "R313") (pin "1") (pinfunction "1_1") (pintype "passive"))
      (node (ref "TVS301") (pin "4") (pinfunction "IO3_4") (pintype "passive"))
    )
    (net (code "14") (name "/ENC2_A_IN") (class "Default")
      (node (ref "P301") (pin "3") (pinfunction "3_3") (pintype "passive"))
      (node (ref "R305") (pin "2") (pinfunction "2_2") (pintype "passive"))
    )
    (net (code "15") (name "/ENC2_B") (class "Default")
      (node (ref "IC301") (pin "5") (pinfunction "2Y_5") (pintype "power_in"))
    )
    (net (code "16") (name "/ENC2_B_5V") (class "Default")
      (node (ref "C313") (pin "2") (pinfunction "2_2") (pintype "passive"))
      (node (ref "IC301") (pin "3") (pinfunction "2A_3") (pintype "power_in"))
      (node (ref "R304") (pin "1") (pinfunction "1_1") (pintype "passive"))
      (node (ref "R317") (pin "1") (pinfunction "1_1") (pintype "passive"))
      (node (ref "TVS301") (pin "3") (pinfunction "IO2_3") (pintype "passive"))
    )
    (net (code "17") (name "/ENC2_B_IN") (class "Default")
      (node (ref "P301") (pin "2") (pinfunction "2_2") (pintype "passive"))
      (node (ref "R304") (pin "2") (pinfunction "2_2") (pintype "passive"))
    )
    (net (code "18") (name "/ENC2_N") (class "Default")
      (node (ref "IC301") (pin "7") (pinfunction "1Y_7") (pintype "power_in"))
    )
    (net (code "19") (name "/ENC2_N_5V") (class "Default")
      (node (ref "C317") (pin "2") (pinfunction "2_2") (pintype "passive"))
      (node (ref "IC301") (pin "1") (pinfunction "1A_1") (pintype "power_in"))
      (node (ref "R303") (pin "1") (pinfunction "1_1") (pintype "passive"))
      (node (ref "R321") (pin "1") (pinfunction "1_1") (pintype "passive"))
      (node (ref "TVS301") (pin "1") (pinfunction "IO1_1") (pintype "passive"))
    )
    (net (code "20") (name "/ENC2_N_IN") (class "Default")
      (node (ref "P301") (pin "1") (pinfunction "1_1") (pintype "passive"))
      (node (ref "R303") (pin "2") (pinfunction "2_2") (pintype "passive"))
    )
    (net (code "21") (name "/HALL_UX") (class "Default")
      (node (ref "IC302") (pin "2") (pinfunction "3Y_2") (pintype "power_in"))
    )
    (net (code "22") (name "/HALL_UX_5V") (class "Default")
      (node (ref "C310") (pin "2") (pinfunction "2_2") (pintype "passive"))
      (node (ref "IC302") (pin "6") (pinfunction "3A_6") (pintype "power_in"))
      (node (ref "R308") (pin "1") (pinfunction "1_1") (pintype "passive"))
      (node (ref "R314") (pin "1") (pinfunction "1_1") (pintype "passive"))
      (node (ref "TVS302") (pin "4") (pinfunction "IO3_4") (pintype "passive"))
    )
    (net (code "23") (name "/HALL_UX_IN") (class "Default")
      (node (ref "P302") (pin "3") (pinfunction "3_3") (pintype "passive"))
      (node (ref "R308") (pin "2") (pinfunction "2_2") (pintype "passive"))
    )
    (net (code "24") (name "/HALL_V") (class "Default")
      (node (ref "IC302") (pin "5") (pinfunction "2Y_5") (pintype "power_in"))
    )
    (net (code "25") (name "/HALL_V_5V") (class "Default")
      (node (ref "C314") (pin "2") (pinfunction "2_2") (pintype "passive"))
      (node (ref "IC302") (pin "3") (pinfunction "2A_3") (pintype "power_in"))
      (node (ref "R307") (pin "1") (pinfunction "1_1") (pintype "passive"))
      (node (ref "R318") (pin "1") (pinfunction "1_1") (pintype "passive"))
      (node (ref "TVS302") (pin "3") (pinfunction "IO2_3") (pintype "passive"))
    )
    (net (code "26") (name "/HALL_V_IN") (class "Default")
      (node (ref "P302") (pin "2") (pinfunction "2_2") (pintype "passive"))
      (node (ref "R307") (pin "2") (pinfunction "2_2") (pintype "passive"))
    )
    (net (code "27") (name "/HALL_WY") (class "Default")
      (node (ref "IC302") (pin "7") (pinfunction "1Y_7") (pintype "power_in"))
    )
    (net (code "28") (name "/HALL_WY_5V") (class "Default")
      (node (ref "C318") (pin "2") (pinfunction "2_2") (pintype "passive"))
      (node (ref "IC302") (pin "1") (pinfunction "1A_1") (pintype "power_in"))
      (node (ref "R306") (pin "1") (pinfunction "1_1") (pintype "passive"))
      (node (ref "R322") (pin "1") (pinfunction "1_1") (pintype "passive"))
      (node (ref "TVS302") (pin "1") (pinfunction "IO1_1") (pintype "passive"))
    )
    (net (code "29") (name "/HALL_WY_IN") (class "Default")
      (node (ref "P302") (pin "1") (pinfunction "1_1") (pintype "passive"))
      (node (ref "R306") (pin "2") (pinfunction "2_2") (pintype "passive"))
    )
    (net (code "30") (name "/REF_H") (class "Default")
      (node (ref "IC303") (pin "5") (pinfunction "2Y_5") (pintype "power_in"))
    )
    (net (code "31") (name "/REF_H_5V") (class "Default")
      (node (ref "C311") (pin "2") (pinfunction "2_2") (pintype "passive"))
      (node (ref "IC303") (pin "6") (pinfunction "3A_6") (pintype "power_in"))
      (node (ref "R311") (pin "1") (pinfunction "1_1") (pintype "passive"))
      (node (ref "R315") (pin "1") (pinfunction "1_1") (pintype "passive"))
      (node (ref "TVS303") (pin "4") (pinfunction "IO3_4") (pintype "passive"))
    )
    (net (code "32") (name "/REF_H_IN") (class "Default")
      (node (ref "P303") (pin "2") (pinfunction "2_2") (pintype "passive"))
      (node (ref "R310") (pin "2") (pinfunction "2_2") (pintype "passive"))
    )
    (net (code "33") (name "/REF_L") (class "Default")
      (node (ref "IC303") (pin "2") (pinfunction "3Y_2") (pintype "power_in"))
    )
    (net (code "34") (name "/REF_L_5V") (class "Default")
      (node (ref "C315") (pin "2") (pinfunction "2_2") (pintype "passive"))
      (node (ref "IC303") (pin "3") (pinfunction "2A_3") (pintype "power_in"))
      (node (ref "R310") (pin "1") (pinfunction "1_1") (pintype "passive"))
      (node (ref "R319") (pin "1") (pinfunction "1_1") (pintype "passive"))
      (node (ref "TVS303") (pin "3") (pinfunction "IO2_3") (pintype "passive"))
    )
    (net (code "35") (name "/REF_L_IN") (class "Default")
      (node (ref "P303") (pin "3") (pinfunction "3_3") (pintype "passive"))
      (node (ref "R311") (pin "2") (pinfunction "2_2") (pintype "passive"))
    )
    (net (code "36") (name "/REF_R") (class "Default")
      (node (ref "IC303") (pin "7") (pinfunction "1Y_7") (pintype "power_in"))
    )
    (net (code "37") (name "/REF_R_5V") (class "Default")
      (node (ref "C319") (pin "2") (pinfunction "2_2") (pintype "passive"))
      (node (ref "IC303") (pin "1") (pinfunction "1A_1") (pintype "power_in"))
      (node (ref "R309") (pin "1") (pinfunction "1_1") (pintype "passive"))
      (node (ref "R323") (pin "1") (pinfunction "1_1") (pintype "passive"))
      (node (ref "TVS303") (pin "1") (pinfunction "IO1_1") (pintype "passive"))
    )
    (net (code "38") (name "/REF_R_IN") (class "Default")
      (node (ref "P303") (pin "1") (pinfunction "1_1") (pintype "passive"))
      (node (ref "R309") (pin "2") (pinfunction "2_2") (pintype "passive"))
    )
    (net (code "39") (name "GND") (class "Default")
      (node (ref "C300") (pin "1") (pinfunction "1_1") (pintype "passive"))
      (node (ref "C301") (pin "1") (pinfunction "1_1") (pintype "passive"))
      (node (ref "C302") (pin "1") (pinfunction "1_1") (pintype "passive"))
      (node (ref "C303") (pin "1") (pinfunction "1_1") (pintype "passive"))
      (node (ref "C304") (pin "2") (pinfunction "2_2") (pintype "passive"))
      (node (ref "C305") (pin "2") (pinfunction "2_2") (pintype "passive"))
      (node (ref "C306") (pin "2") (pinfunction "2_2") (pintype "passive"))
      (node (ref "C307") (pin "2") (pinfunction "2_2") (pintype "passive"))
      (node (ref "C308") (pin "1") (pinfunction "1_1") (pintype "passive"))
      (node (ref "C309") (pin "1") (pinfunction "1_1") (pintype "passive"))
      (node (ref "C310") (pin "1") (pinfunction "1_1") (pintype "passive"))
      (node (ref "C311") (pin "1") (pinfunction "1_1") (pintype "passive"))
      (node (ref "C312") (pin "1") (pinfunction "1_1") (pintype "passive"))
      (node (ref "C313") (pin "1") (pinfunction "1_1") (pintype "passive"))
      (node (ref "C314") (pin "1") (pinfunction "1_1") (pintype "passive"))
      (node (ref "C315") (pin "1") (pinfunction "1_1") (pintype "passive"))
      (node (ref "C316") (pin "1") (pinfunction "1_1") (pintype "passive"))
      (node (ref "C317") (pin "1") (pinfunction "1_1") (pintype "passive"))
      (node (ref "C318") (pin "1") (pinfunction "1_1") (pintype "passive"))
      (node (ref "C319") (pin "1") (pinfunction "1_1") (pintype "passive"))
      (node (ref "C320") (pin "1") (pinfunction "1_1") (pintype "passive"))
      (node (ref "C321") (pin "1") (pinfunction "1_1") (pintype "passive"))
      (node (ref "C322") (pin "1") (pinfunction "1_1") (pintype "passive"))
      (node (ref "C323") (pin "1") (pinfunction "1_1") (pintype "passive"))
      (node (ref "IC300") (pin "4") (pinfunction "GND_4") (pintype "power_in"))
      (node (ref "IC301") (pin "4") (pinfunction "GND_4") (pintype "power_in"))
      (node (ref "IC302") (pin "4") (pinfunction "GND_4") (pintype "power_in"))
      (node (ref "IC303") (pin "4") (pinfunction "GND_4") (pintype "power_in"))
      (node (ref "P300") (pin "4") (pinfunction "4_4") (pintype "passive"))
      (node (ref "P301") (pin "4") (pinfunction "4_4") (pintype "passive"))
      (node (ref "P302") (pin "4") (pinfunction "4_4") (pintype "passive"))
      (node (ref "P303") (pin "4") (pinfunction "4_4") (pintype "passive"))
      (node (ref "TVS300") (pin "2") (pinfunction "GND_2") (pintype "passive"))
      (node (ref "TVS301") (pin "2") (pinfunction "GND_2") (pintype "passive"))
      (node (ref "TVS302") (pin "2") (pinfunction "GND_2") (pintype "passive"))
      (node (ref "TVS303") (pin "2") (pinfunction "GND_2") (pintype "passive"))
    )
    (net (code "40") (name "unconnected-(TVS300-IO4-Pad6)") (class "Default")
      (node (ref "TVS300") (pin "6") (pinfunction "IO4_6") (pintype "passive"))
    )
    (net (code "41") (name "unconnected-(TVS301-IO4-Pad6)") (class "Default")
      (node (ref "TVS301") (pin "6") (pinfunction "IO4_6") (pintype "passive"))
    )
    (net (code "42") (name "unconnected-(TVS302-IO4-Pad6)") (class "Default")
      (node (ref "TVS302") (pin "6") (pinfunction "IO4_6") (pintype "passive"))
    )
    (net (code "43") (name "unconnected-(TVS303-IO4-Pad6)") (class "Default")
      (node (ref "TVS303") (pin "6") (pinfunction "IO4_6") (pintype "passive"))
    )
  )
)
